# Temp_hum_sensor.net
KiCad netlist of a schematic drawn in Altium Designer
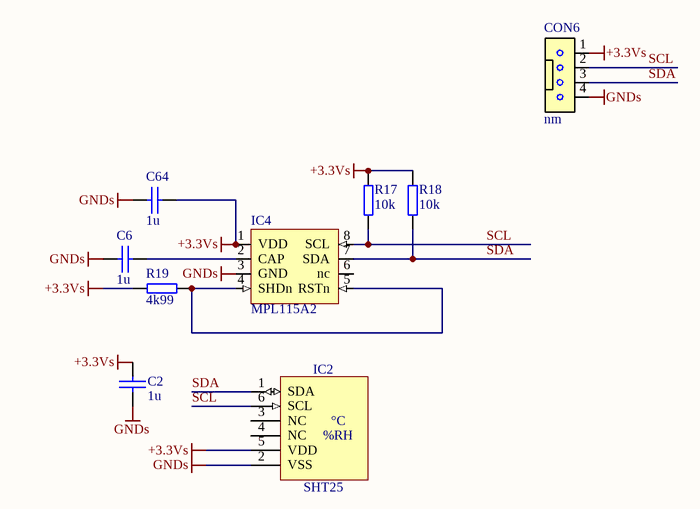
[diagram p0: Temp_hum_sensor.SchDoc]

(export (version "E")
  (design (tool "Eeschema 10.0.6"))
  (components
    (comp (ref "C2")
      (value "1u")
      (footprint "0603C")
      (description "Capacitor SMD")
      (libsource (lib "LIBRARY_SCH") (part "CAP_SMD_0603"))
    )
    (comp (ref "C6")
      (value "1u")
      (footprint "0603C")
      (description "Capacitor SMD")
      (libsource (lib "LIBRARY_SCH") (part "CAP_SMD_0603"))
    )
    (comp (ref "C64")
      (value "1u")
      (footprint "0603C")
      (description "Capacitor SMD")
      (libsource (lib "LIBRARY_SCH") (part "CAP_SMD_0603"))
    )
    (comp (ref "CON6")
      (value "nm")
      (footprint "WZ04S")
      (description "2.54mm crimped terminal header")
      (libsource (lib "ProjectLib") (part "CON_4_2.54_key"))
    )
    (comp (ref "IC2")
      (value "SHT25")
      (footprint "SENSIRION_SHT2X")
      (description "Humidity and Temperature Sensor IC")
      (fields (field (name "MANUFACTURER") "SENSIRION") (field (name "AUTHOR") "CERN DEM JLC"))
      (libsource (lib "ICs And Semiconductors") (part "SHT2x"))
    )
    (comp (ref "IC4")
      (value "MPL115A2")
      (footprint "LGA8")
      (description "Miniature I2C Digital Barometer")
      (libsource (lib "LIBRARY_SCH") (part "SENS_MPL115A2"))
    )
    (comp (ref "R17")
      (value "10k")
      (footprint "0402R")
      (description "SMD Resistor")
      (libsource (lib "LIBRARY_SCH") (part "RES_0402"))
    )
    (comp (ref "R18")
      (value "10k")
      (footprint "0402R")
      (description "SMD Resistor")
      (libsource (lib "LIBRARY_SCH") (part "RES_0402"))
    )
    (comp (ref "R19")
      (value "4k99")
      (footprint "0603R")
      (description "SMD Resistor")
      (libsource (lib "LIBRARY_SCH") (part "RES_0603"))
    )
  )
  (nets
    (net (code "1") (name "+3.3Vs") (class "Default")
      (node (ref "C2") (pin "2") (pinfunction "2_2") (pintype "passive"))
      (node (ref "C64") (pin "2") (pinfunction "2_2") (pintype "passive"))
      (node (ref "CON6") (pin "1") (pinfunction "1_1") (pintype "bidirectional"))
      (node (ref "IC2") (pin "5") (pinfunction "VDD_5") (pintype "power_in"))
      (node (ref "IC4") (pin "1") (pinfunction "VDD_1") (pintype "power_in"))
      (node (ref "R17") (pin "2") (pinfunction "2_2") (pintype "passive"))
      (node (ref "R18") (pin "2") (pinfunction "2_2") (pintype "passive"))
      (node (ref "R19") (pin "2") (pinfunction "2_2") (pintype "passive"))
    )
    (net (code "2") (name "/SCL") (class "Default")
      (node (ref "CON6") (pin "2") (pinfunction "2_2") (pintype "bidirectional"))
      (node (ref "IC2") (pin "6") (pinfunction "SCL_6") (pintype "input"))
      (node (ref "IC4") (pin "8") (pinfunction "SCL_8") (pintype "input"))
      (node (ref "R17") (pin "1") (pinfunction "1_1") (pintype "passive"))
    )
    (net (code "3") (name "/SDA") (class "Default")
      (node (ref "CON6") (pin "3") (pinfunction "3_3") (pintype "bidirectional"))
      (node (ref "IC2") (pin "1") (pinfunction "SDA_1") (pintype "bidirectional"))
      (node (ref "IC4") (pin "7") (pinfunction "SDA_7") (pintype "bidirectional"))
      (node (ref "R18") (pin "1") (pinfunction "1_1") (pintype "passive"))
    )
    (net (code "4") (name "GNDs") (class "Default")
      (node (ref "C2") (pin "1") (pinfunction "1_1") (pintype "passive"))
      (node (ref "C6") (pin "1") (pinfunction "1_1") (pintype "passive"))
      (node (ref "C64") (pin "1") (pinfunction "1_1") (pintype "passive"))
      (node (ref "CON6") (pin "4") (pinfunction "4_4") (pintype "bidirectional"))
      (node (ref "IC2") (pin "2") (pinfunction "VSS_2") (pintype "power_in"))
      (node (ref "IC4") (pin "3") (pinfunction "GND_3") (pintype "power_in"))
    )
    (net (code "5") (name "Net-(IC4-CAP)") (class "Default")
      (node (ref "C6") (pin "2") (pinfunction "2_2") (pintype "passive"))
      (node (ref "IC4") (pin "2") (pinfunction "CAP_2") (pintype "passive"))
    )
    (net (code "6") (name "Net-(IC4-RSTn)") (class "Default")
      (node (ref "IC4") (pin "4") (pinfunction "SHDn_4") (pintype "input"))
      (node (ref "IC4") (pin "5") (pinfunction "RSTn_5") (pintype "input"))
      (node (ref "R19") (pin "1") (pinfunction "1_1") (pintype "passive"))
    )
    (net (code "7") (name "unconnected-(IC2-NC-Pad3)") (class "Default")
      (node (ref "IC2") (pin "3") (pinfunction "NC_3") (pintype "passive"))
    )
    (net (code "8") (name "unconnected-(IC2-NC-Pad4)") (class "Default")
      (node (ref "IC2") (pin "4") (pinfunction "NC_4") (pintype "passive"))
    )
    (net (code "9") (name "unconnected-(IC4-nc-Pad6)") (class "Default")
      (node (ref "IC4") (pin "6") (pinfunction "nc_6") (pintype "passive"))
    )
  )
)
